# Power.net
KiCad netlist of a schematic drawn in Altium Designer
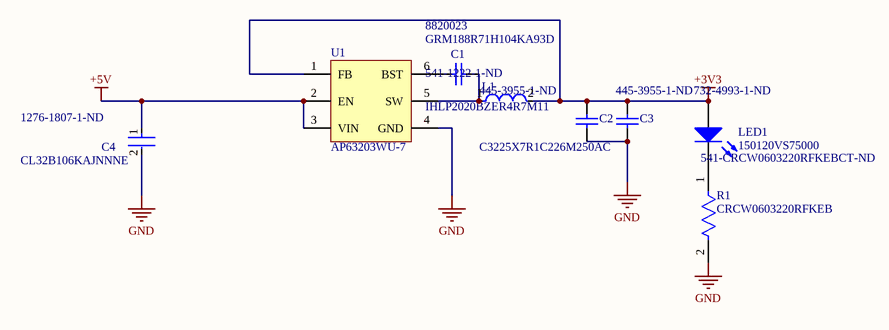
[diagram p0: Power.SchDoc]

(export (version "E")
  (design (tool "Eeschema 10.0.6"))
  (components
    (comp (ref "C1")
      (value "GRM188R71H104KA93D")
      (footprint "CAPC1608X90X35ML10T15")
      (description "Chip Capacitor, 0.1 uF, +/- 10%, 50 V, -55 to 125 degC, 0603 (1608 Metric), RoHS, Tape and Reel")
      (fields
        (field (name "TOLERANCE") "10%")
        (field (name "VOLTAGE") "50V")
        (field (name "SUPPLIER PART NUMBER 1") "8820023")
      )
      (libsource (lib "Altium Content Vault") (part "CAP-NP-2"))
    )
    (comp (ref "C2")
      (value "C3225X7R1C226M250AC")
      (footprint "CAPC3225X280X20LL40")
      (description "Multilayer Ceramic Capacitor, 22 uF, 16 V, -55 to 125 degC, 2-Pin SMD, RoHS, Tape and Reel")
      (fields
        (field (name "TOLERANCE") "±20%")
        (field (name "PCN PART NUMBER") "MLCCPartNumberChange30/Nov/2012")
        (field (name "SUPPLIER PART NUMBER 1") "445-3955-1-ND")
      )
      (libsource (lib "Altium Content Vault") (part "CAP-NP-2"))
    )
    (comp (ref "C3")
      (value "C3225X7R1C226M250AC")
      (footprint "CAPC3225X280X20LL40")
      (description "Multilayer Ceramic Capacitor, 22 uF, 16 V, -55 to 125 degC, 2-Pin SMD, RoHS, Tape and Reel")
      (fields
        (field (name "TOLERANCE") "±20%")
        (field (name "PCN PART NUMBER") "MLCCPartNumberChange30/Nov/2012")
        (field (name "SUPPLIER PART NUMBER 1") "445-3955-1-ND")
      )
      (libsource (lib "Altium Content Vault") (part "CAP-NP-2"))
    )
    (comp (ref "C4")
      (value "CL32B106KAJNNNE")
      (footprint "FP-CL32-IPC_C")
      (description "Cap Ceramic 10uF 25V X7R ±10% SMD 1210 +125°C Embossed T/R")
      (fields
        (field (name "TOLERANCE") "10%")
        (field (name "VOLTAGE") "25V")
        (field (name "SUPPLIER PART NUMBER 1") "1276-1807-1-ND")
      )
      (libsource (lib "Altium Content Vault") (part "b4654b650e69147ec39a6b967a45e02"))
    )
    (comp (ref "L1")
      (value "IHLP2020BZER4R7M11")
      (footprint "FP-IHLP-2020BZ-FP_1_905x2-MFG")
      (description "Fixed Inductors Commercial Low DCR Series 4.7uH 3.2A 81.3mΩ 20%")
      (fields
        (field (name "TOLERANCE") "20%")
        (field (name "SUPPLIER PART NUMBER 1") "541-1222-1-ND")
        (field (name "MANUFACTURER") "Vishay Dale")
      )
      (libsource (lib "Altium Content Vault") (part "725321dda6339637d4d059423bc1c3c"))
    )
    (comp (ref "LED1")
      (value "150120VS75000")
      (footprint "1206_A")
      (description "LED, Green, 570 nm, 2 V, 30 mA, 40 mcd")
      (fields
        (field (name "MANUFACTURER") "Wuerth Elektronik")
        (field (name "SUPPLIER PART NUMBER 1") "732-4993-1-ND")
      )
      (libsource (lib "Altium Content Vault") (part "WE-LED_K1A2-2"))
    )
    (comp (ref "R1")
      (value "CRCW0603220RFKEB")
      (footprint "FP-CRCW0603-e3-MFG")
      (description "RES Thick Film, 220Ω, 1%, 0.1W, 100ppm/°C, 0603")
      (fields
        (field (name "TOLERANCE") "1%")
        (field (name "SUPPLIER PART NUMBER 1") "541-CRCW0603220RFKEBCT-ND")
        (field (name "MANUFACTURER") "Vishay Dale")
      )
      (libsource (lib "Altium Content Vault") (part "1029c3af85768c4190bb7ad29bc67b5"))
    )
    (comp (ref "U1")
      (value "3.3V SW Reg (AP63203WU-7)")
      (footprint "TSOT26")
      (description "AP63203 Series 3.3 V 2 A SMT Fixed Low IQ Synchronous Buck - TSOT-26")
      (fields
        (field (name "MANUFACTURER PART NUMBER 1") "AP63203WU-7")
        (field (name "MANUFACTURER") "Diodes")
        (field (name "MANUFACTURER PART NUMBER") "AP63203WU-7")
      )
      (libsource (lib "BrewController") (part "3.3V SW Reg (AP63203WU-7)"))
    )
  )
  (nets
    (net (code "1") (name "+3V3") (class "Default")
      (node (ref "C2") (pin "2") (pinfunction "2_2") (pintype "passive"))
      (node (ref "C3") (pin "2") (pinfunction "2_2") (pintype "passive"))
      (node (ref "L1") (pin "2") (pinfunction "2_2") (pintype "passive"))
      (node (ref "LED1") (pin "2") (pinfunction "A_2") (pintype "passive"))
      (node (ref "U1") (pin "1") (pinfunction "FB_1") (pintype "passive"))
    )
    (net (code "2") (name "+5V") (class "Default")
      (node (ref "C4") (pin "1") (pinfunction "1_1") (pintype "passive"))
      (node (ref "U1") (pin "2") (pinfunction "EN_2") (pintype "passive"))
      (node (ref "U1") (pin "3") (pinfunction "VIN_3") (pintype "passive"))
    )
    (net (code "3") (name "GND") (class "Default")
      (node (ref "C2") (pin "1") (pinfunction "1_1") (pintype "passive"))
      (node (ref "C3") (pin "1") (pinfunction "1_1") (pintype "passive"))
      (node (ref "C4") (pin "2") (pinfunction "2_2") (pintype "passive"))
      (node (ref "R1") (pin "2") (pinfunction "2_2") (pintype "passive"))
      (node (ref "U1") (pin "4") (pinfunction "GND_4") (pintype "passive"))
    )
    (net (code "4") (name "Net-(LED1-K)") (class "Default")
      (node (ref "LED1") (pin "1") (pinfunction "K_1") (pintype "passive"))
      (node (ref "R1") (pin "1") (pinfunction "1_1") (pintype "passive"))
    )
    (net (code "5") (name "Net-(U1-BST)") (class "Default")
      (node (ref "C1") (pin "2") (pinfunction "2_2") (pintype "passive"))
      (node (ref "U1") (pin "6") (pinfunction "BST_6") (pintype "passive"))
    )
    (net (code "6") (name "Net-(U1-SW)") (class "Default")
      (node (ref "C1") (pin "1") (pinfunction "1_1") (pintype "passive"))
      (node (ref "L1") (pin "1") (pinfunction "1_1") (pintype "passive"))
      (node (ref "U1") (pin "5") (pinfunction "SW_5") (pintype "passive"))
    )
  )
)
